# rev_A.net
KiCad netlist of a schematic drawn in EAGLE
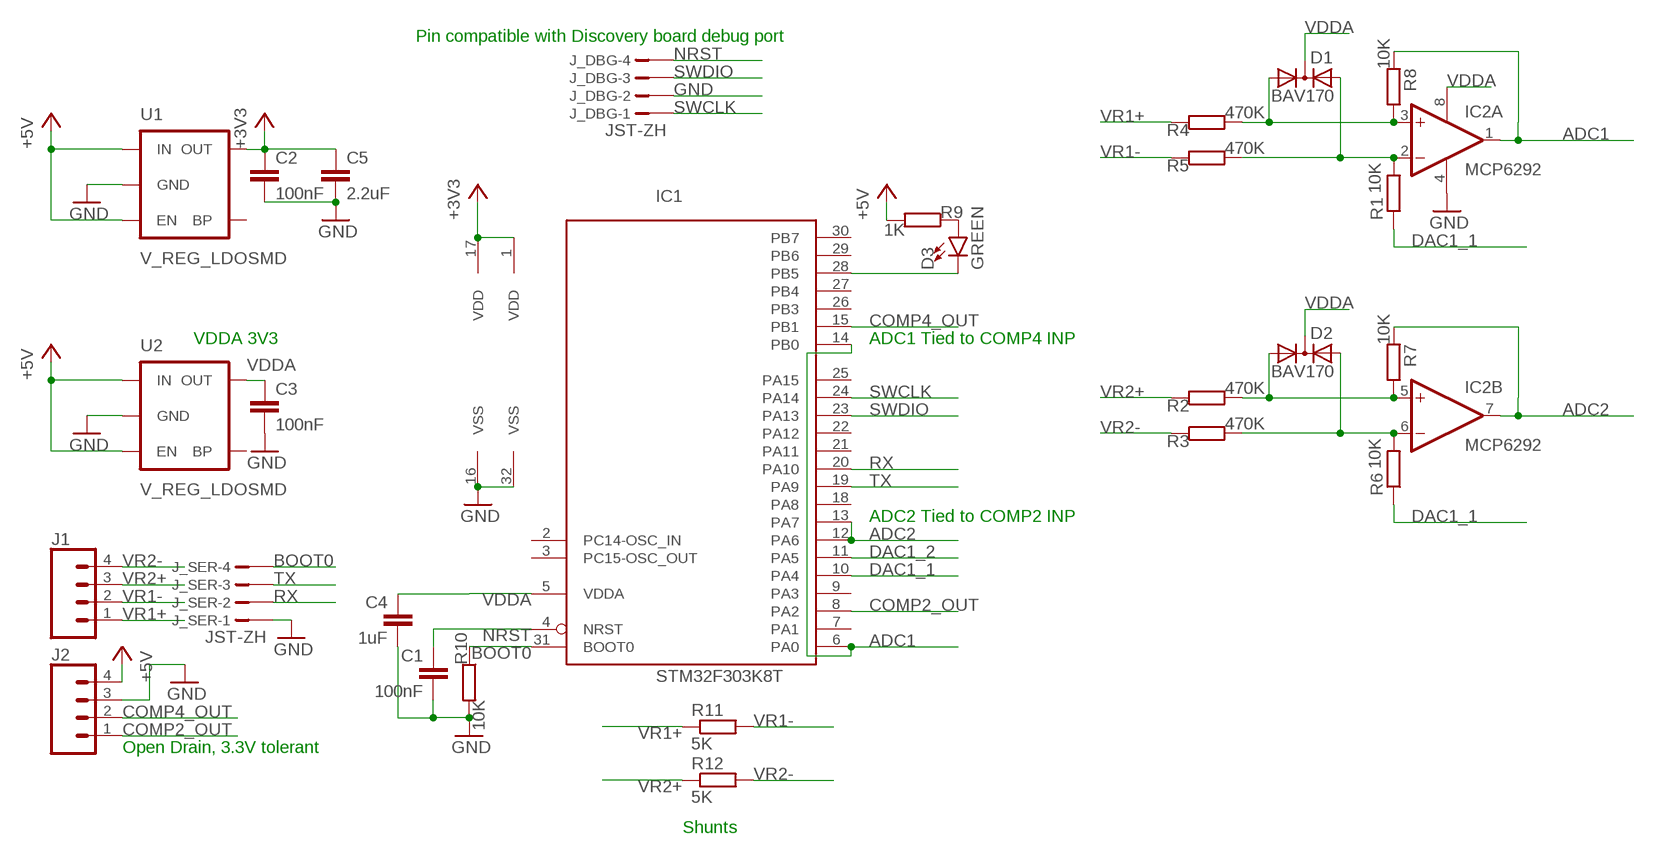
[diagram p0: schematic, sheet 1]

(export (version "E")
  (design (tool "Eeschema 10.0.6"))
  (components
    (comp (ref "C1")
      (value "100nF")
      (footprint "eagle-import:C0603")
      (libsource (lib "eagle-import") (part "C-EUC0603"))
    )
    (comp (ref "C2")
      (value "100nF")
      (footprint "eagle-import:C0603")
      (libsource (lib "eagle-import") (part "C-EUC0603"))
    )
    (comp (ref "C3")
      (value "100nF")
      (footprint "eagle-import:C0603")
      (libsource (lib "eagle-import") (part "C-EUC0603"))
    )
    (comp (ref "C4")
      (value "1uF")
      (footprint "eagle-import:C0603")
      (libsource (lib "eagle-import") (part "C-EUC0603"))
    )
    (comp (ref "C5")
      (value "2.2uF")
      (footprint "eagle-import:C0603")
      (libsource (lib "eagle-import") (part "C-EUC0603"))
    )
    (comp (ref "D1")
      (value "BAV170")
      (footprint "eagle-import:SOT23")
      (libsource (lib "eagle-import") (part "DIODE-2AC|CASOT23"))
    )
    (comp (ref "D2")
      (value "BAV170")
      (footprint "eagle-import:SOT23")
      (libsource (lib "eagle-import") (part "DIODE-2AC|CASOT23"))
    )
    (comp (ref "D3")
      (value "GREEN")
      (footprint "eagle-import:LED-0603")
      (libsource (lib "eagle-import") (part "LED-GREEN0603"))
    )
    (comp (ref "IC1")
      (value "STM32F303K8T")
      (footprint "eagle-import:LQFP32")
      (libsource (lib "eagle-import") (part "STM32L051KT6"))
    )
    (comp (ref "IC2")
      (value "MCP6292")
      (footprint "eagle-import:SO08")
      (libsource (lib "eagle-import") (part "MCP602SN"))
    )
    (comp (ref "J1")
      (value "CONN_04LOCK")
      (footprint "eagle-import:1X04_LOCK")
      (libsource (lib "eagle-import") (part "CONN_04LOCK"))
    )
    (comp (ref "J2")
      (value "CONN_04LOCK")
      (footprint "eagle-import:1X04_LOCK")
      (libsource (lib "eagle-import") (part "CONN_04LOCK"))
    )
    (comp (ref "J_DBG")
      (value "JST-ZH")
      (footprint "eagle-import:B4B-ZR")
      (fields (field (name "MF") "FARNELL") (field (name "MPN") "B4B-ZR(LF)(SN)"))
      (libsource (lib "eagle-import") (part "?4B-ZRB"))
    )
    (comp (ref "J_SER")
      (value "JST-ZH")
      (footprint "eagle-import:B4B-ZR")
      (fields (field (name "MF") "FARNELL") (field (name "MPN") "B4B-ZR(LF)(SN)"))
      (libsource (lib "eagle-import") (part "?4B-ZRB"))
    )
    (comp (ref "R1")
      (value "10K")
      (footprint "eagle-import:R0603")
      (libsource (lib "eagle-import") (part "R-EU_R0603"))
    )
    (comp (ref "R2")
      (value "470K")
      (footprint "eagle-import:R0603")
      (libsource (lib "eagle-import") (part "R-EU_R0603"))
    )
    (comp (ref "R3")
      (value "470K")
      (footprint "eagle-import:R0603")
      (libsource (lib "eagle-import") (part "R-EU_R0603"))
    )
    (comp (ref "R4")
      (value "470K")
      (footprint "eagle-import:R0603")
      (libsource (lib "eagle-import") (part "R-EU_R0603"))
    )
    (comp (ref "R5")
      (value "470K")
      (footprint "eagle-import:R0603")
      (libsource (lib "eagle-import") (part "R-EU_R0603"))
    )
    (comp (ref "R6")
      (value "10K")
      (footprint "eagle-import:R0603")
      (libsource (lib "eagle-import") (part "R-EU_R0603"))
    )
    (comp (ref "R7")
      (value "10K")
      (footprint "eagle-import:R0603")
      (libsource (lib "eagle-import") (part "R-EU_R0603"))
    )
    (comp (ref "R8")
      (value "10K")
      (footprint "eagle-import:R0603")
      (libsource (lib "eagle-import") (part "R-EU_R0603"))
    )
    (comp (ref "R9")
      (value "1K")
      (footprint "eagle-import:R0603")
      (libsource (lib "eagle-import") (part "R-EU_R0603"))
    )
    (comp (ref "R10")
      (value "10K")
      (footprint "eagle-import:R0603")
      (libsource (lib "eagle-import") (part "R-EU_R0603"))
    )
    (comp (ref "R11")
      (value "5K")
      (footprint "eagle-import:0411_12")
      (libsource (lib "eagle-import") (part "R-EU_0411/12"))
    )
    (comp (ref "R12")
      (value "5K")
      (footprint "eagle-import:0411_12")
      (libsource (lib "eagle-import") (part "R-EU_0411/12"))
    )
    (comp (ref "U1")
      (value "V_REG_LDOSMD")
      (footprint "eagle-import:SOT23-5")
      (libsource (lib "eagle-import") (part "V_REG_LDOSMD"))
    )
    (comp (ref "U2")
      (value "V_REG_LDOSMD")
      (footprint "eagle-import:SOT23-5")
      (libsource (lib "eagle-import") (part "V_REG_LDOSMD"))
    )
  )
  (nets
    (net (code "1") (name "+3V3") (class "Default")
      (node (ref "C2") (pin "1") (pinfunction "1_1") (pintype "passive"))
      (node (ref "C5") (pin "1") (pinfunction "1_1") (pintype "passive"))
      (node (ref "IC1") (pin "1") (pinfunction "VDD_1") (pintype "power_in"))
      (node (ref "IC1") (pin "17") (pinfunction "VDD_17") (pintype "power_in"))
      (node (ref "U1") (pin "5") (pinfunction "OUT_5") (pintype "passive"))
    )
    (net (code "2") (name "+5V") (class "Default")
      (node (ref "J2") (pin "4") (pinfunction "4_4") (pintype "passive"))
      (node (ref "R9") (pin "2") (pinfunction "2_2") (pintype "passive"))
      (node (ref "U1") (pin "1") (pinfunction "IN_1") (pintype "input"))
      (node (ref "U1") (pin "3") (pinfunction "EN_3") (pintype "input"))
      (node (ref "U2") (pin "1") (pinfunction "IN_1") (pintype "input"))
      (node (ref "U2") (pin "3") (pinfunction "EN_3") (pintype "input"))
    )
    (net (code "3") (name "/ADC1") (class "Default")
      (node (ref "IC1") (pin "14") (pinfunction "PB0_14") (pintype "bidirectional"))
      (node (ref "IC1") (pin "6") (pinfunction "PA0_6") (pintype "bidirectional"))
      (node (ref "IC2") (pin "1") (pinfunction "OUT_1") (pintype "output"))
      (node (ref "R8") (pin "2") (pinfunction "2_2") (pintype "passive"))
    )
    (net (code "4") (name "/ADC2") (class "Default")
      (node (ref "IC1") (pin "12") (pinfunction "PA6_12") (pintype "bidirectional"))
      (node (ref "IC1") (pin "13") (pinfunction "PA7_13") (pintype "bidirectional"))
      (node (ref "IC2") (pin "7") (pinfunction "OUT_7") (pintype "output"))
      (node (ref "R7") (pin "2") (pinfunction "2_2") (pintype "passive"))
    )
    (net (code "5") (name "/BOOT0") (class "Default")
      (node (ref "IC1") (pin "31") (pinfunction "BOOT0_31") (pintype "input"))
      (node (ref "J_SER") (pin "4") (pinfunction "1_4") (pintype "passive"))
      (node (ref "R10") (pin "1") (pinfunction "1_1") (pintype "passive"))
    )
    (net (code "6") (name "/COMP2_OUT") (class "Default")
      (node (ref "IC1") (pin "8") (pinfunction "PA2_8") (pintype "bidirectional"))
      (node (ref "J2") (pin "1") (pinfunction "1_1") (pintype "passive"))
    )
    (net (code "7") (name "/COMP4_OUT") (class "Default")
      (node (ref "IC1") (pin "15") (pinfunction "PB1_15") (pintype "bidirectional"))
      (node (ref "J2") (pin "2") (pinfunction "2_2") (pintype "passive"))
    )
    (net (code "8") (name "/DAC1_1") (class "Default")
      (node (ref "IC1") (pin "10") (pinfunction "PA4_10") (pintype "bidirectional"))
      (node (ref "R1") (pin "1") (pinfunction "1_1") (pintype "passive"))
      (node (ref "R6") (pin "1") (pinfunction "1_1") (pintype "passive"))
    )
    (net (code "9") (name "/DAC1_2") (class "Default")
      (node (ref "IC1") (pin "11") (pinfunction "PA5_11") (pintype "bidirectional"))
    )
    (net (code "10") (name "/NRST") (class "Default")
      (node (ref "C1") (pin "1") (pinfunction "1_1") (pintype "passive"))
      (node (ref "IC1") (pin "4") (pinfunction "NRST_4") (pintype "bidirectional"))
      (node (ref "J_DBG") (pin "4") (pinfunction "1_4") (pintype "passive"))
    )
    (net (code "11") (name "/RX") (class "Default")
      (node (ref "IC1") (pin "20") (pinfunction "PA10_20") (pintype "bidirectional"))
      (node (ref "J_SER") (pin "2") (pinfunction "1_2") (pintype "passive"))
    )
    (net (code "12") (name "/SWCLK") (class "Default")
      (node (ref "IC1") (pin "24") (pinfunction "PA14_24") (pintype "bidirectional"))
      (node (ref "J_DBG") (pin "1") (pinfunction "1_1") (pintype "passive"))
    )
    (net (code "13") (name "/SWDIO") (class "Default")
      (node (ref "IC1") (pin "23") (pinfunction "PA13_23") (pintype "bidirectional"))
      (node (ref "J_DBG") (pin "3") (pinfunction "1_3") (pintype "passive"))
    )
    (net (code "14") (name "/TX") (class "Default")
      (node (ref "IC1") (pin "19") (pinfunction "PA9_19") (pintype "bidirectional"))
      (node (ref "J_SER") (pin "3") (pinfunction "1_3") (pintype "passive"))
    )
    (net (code "15") (name "/VDDA") (class "Default")
      (node (ref "C3") (pin "1") (pinfunction "1_1") (pintype "passive"))
      (node (ref "C4") (pin "1") (pinfunction "1_1") (pintype "passive"))
      (node (ref "D1") (pin "3") (pinfunction "C_3") (pintype "passive"))
      (node (ref "D2") (pin "3") (pinfunction "C_3") (pintype "passive"))
      (node (ref "IC1") (pin "5") (pinfunction "VDDA_5") (pintype "power_in"))
      (node (ref "IC2") (pin "8") (pinfunction "V+_8") (pintype "power_in"))
      (node (ref "U2") (pin "5") (pinfunction "OUT_5") (pintype "passive"))
    )
    (net (code "16") (name "/VR1+") (class "Default")
      (node (ref "J1") (pin "1") (pinfunction "1_1") (pintype "passive"))
      (node (ref "R11") (pin "1") (pinfunction "1_1") (pintype "passive"))
      (node (ref "R4") (pin "1") (pinfunction "1_1") (pintype "passive"))
    )
    (net (code "17") (name "/VR1-") (class "Default")
      (node (ref "J1") (pin "2") (pinfunction "2_2") (pintype "passive"))
      (node (ref "R11") (pin "2") (pinfunction "2_2") (pintype "passive"))
      (node (ref "R5") (pin "1") (pinfunction "1_1") (pintype "passive"))
    )
    (net (code "18") (name "/VR2+") (class "Default")
      (node (ref "J1") (pin "3") (pinfunction "3_3") (pintype "passive"))
      (node (ref "R12") (pin "1") (pinfunction "1_1") (pintype "passive"))
      (node (ref "R2") (pin "1") (pinfunction "1_1") (pintype "passive"))
    )
    (net (code "19") (name "/VR2-") (class "Default")
      (node (ref "J1") (pin "4") (pinfunction "4_4") (pintype "passive"))
      (node (ref "R12") (pin "2") (pinfunction "2_2") (pintype "passive"))
      (node (ref "R3") (pin "1") (pinfunction "1_1") (pintype "passive"))
    )
    (net (code "20") (name "GND") (class "Default")
      (node (ref "C1") (pin "2") (pinfunction "2_2") (pintype "passive"))
      (node (ref "C2") (pin "2") (pinfunction "2_2") (pintype "passive"))
      (node (ref "C3") (pin "2") (pinfunction "2_2") (pintype "passive"))
      (node (ref "C4") (pin "2") (pinfunction "2_2") (pintype "passive"))
      (node (ref "C5") (pin "2") (pinfunction "2_2") (pintype "passive"))
      (node (ref "IC1") (pin "16") (pinfunction "VSS_16") (pintype "power_in"))
      (node (ref "IC1") (pin "32") (pinfunction "VSS_32") (pintype "power_in"))
      (node (ref "IC2") (pin "4") (pinfunction "V-_4") (pintype "power_in"))
      (node (ref "J2") (pin "3") (pinfunction "3_3") (pintype "passive"))
      (node (ref "J_DBG") (pin "2") (pinfunction "1_2") (pintype "passive"))
      (node (ref "J_SER") (pin "1") (pinfunction "1_1") (pintype "passive"))
      (node (ref "R10") (pin "2") (pinfunction "2_2") (pintype "passive"))
      (node (ref "U1") (pin "2") (pinfunction "GND_2") (pintype "input"))
      (node (ref "U2") (pin "2") (pinfunction "GND_2") (pintype "input"))
    )
    (net (code "21") (name "Net-(D1-A1)") (class "Default")
      (node (ref "D1") (pin "1") (pinfunction "A1_1") (pintype "passive"))
      (node (ref "IC2") (pin "3") (pinfunction "+IN_3") (pintype "input"))
      (node (ref "R4") (pin "2") (pinfunction "2_2") (pintype "passive"))
      (node (ref "R8") (pin "1") (pinfunction "1_1") (pintype "passive"))
    )
    (net (code "22") (name "Net-(D1-A2)") (class "Default")
      (node (ref "D1") (pin "2") (pinfunction "A2_2") (pintype "passive"))
      (node (ref "IC2") (pin "2") (pinfunction "-IN_2") (pintype "input"))
      (node (ref "R1") (pin "2") (pinfunction "2_2") (pintype "passive"))
      (node (ref "R5") (pin "2") (pinfunction "2_2") (pintype "passive"))
    )
    (net (code "23") (name "Net-(D2-A1)") (class "Default")
      (node (ref "D2") (pin "1") (pinfunction "A1_1") (pintype "passive"))
      (node (ref "IC2") (pin "5") (pinfunction "+IN_5") (pintype "input"))
      (node (ref "R2") (pin "2") (pinfunction "2_2") (pintype "passive"))
      (node (ref "R7") (pin "1") (pinfunction "1_1") (pintype "passive"))
    )
    (net (code "24") (name "Net-(D2-A2)") (class "Default")
      (node (ref "D2") (pin "2") (pinfunction "A2_2") (pintype "passive"))
      (node (ref "IC2") (pin "6") (pinfunction "-IN_6") (pintype "input"))
      (node (ref "R3") (pin "2") (pinfunction "2_2") (pintype "passive"))
      (node (ref "R6") (pin "2") (pinfunction "2_2") (pintype "passive"))
    )
    (net (code "25") (name "Net-(D3-PadA)") (class "Default")
      (node (ref "D3") (pin "A") (pinfunction "A_A") (pintype "passive"))
      (node (ref "R9") (pin "1") (pinfunction "1_1") (pintype "passive"))
    )
    (net (code "26") (name "Net-(IC1A-PB5)") (class "Default")
      (node (ref "D3") (pin "C") (pinfunction "C_C") (pintype "passive"))
      (node (ref "IC1") (pin "28") (pinfunction "PB5_28") (pintype "bidirectional"))
    )
    (net (code "27") (name "unconnected-(IC1A-PA1-Pad7)") (class "Default")
      (node (ref "IC1") (pin "7") (pinfunction "PA1_7") (pintype "bidirectional"))
    )
    (net (code "28") (name "unconnected-(IC1A-PA3-Pad9)") (class "Default")
      (node (ref "IC1") (pin "9") (pinfunction "PA3_9") (pintype "bidirectional"))
    )
    (net (code "29") (name "unconnected-(IC1A-PA8-Pad18)") (class "Default")
      (node (ref "IC1") (pin "18") (pinfunction "PA8_18") (pintype "bidirectional"))
    )
    (net (code "30") (name "unconnected-(IC1A-PA11-Pad21)") (class "Default")
      (node (ref "IC1") (pin "21") (pinfunction "PA11_21") (pintype "bidirectional"))
    )
    (net (code "31") (name "unconnected-(IC1A-PA12-Pad22)") (class "Default")
      (node (ref "IC1") (pin "22") (pinfunction "PA12_22") (pintype "bidirectional"))
    )
    (net (code "32") (name "unconnected-(IC1A-PA15-Pad25)") (class "Default")
      (node (ref "IC1") (pin "25") (pinfunction "PA15_25") (pintype "bidirectional"))
    )
    (net (code "33") (name "unconnected-(IC1A-PB3-Pad26)") (class "Default")
      (node (ref "IC1") (pin "26") (pinfunction "PB3_26") (pintype "bidirectional"))
    )
    (net (code "34") (name "unconnected-(IC1A-PB4-Pad27)") (class "Default")
      (node (ref "IC1") (pin "27") (pinfunction "PB4_27") (pintype "bidirectional"))
    )
    (net (code "35") (name "unconnected-(IC1A-PB6-Pad29)") (class "Default")
      (node (ref "IC1") (pin "29") (pinfunction "PB6_29") (pintype "bidirectional"))
    )
    (net (code "36") (name "unconnected-(IC1A-PB7-Pad30)") (class "Default")
      (node (ref "IC1") (pin "30") (pinfunction "PB7_30") (pintype "bidirectional"))
    )
    (net (code "37") (name "unconnected-(IC1A-PC14-OSC_IN-Pad2)") (class "Default")
      (node (ref "IC1") (pin "2") (pinfunction "PC14-OSC_IN_2") (pintype "bidirectional"))
    )
    (net (code "38") (name "unconnected-(IC1A-PC15-OSC_OUT-Pad3)") (class "Default")
      (node (ref "IC1") (pin "3") (pinfunction "PC15-OSC_OUT_3") (pintype "bidirectional"))
    )
    (net (code "39") (name "unconnected-(U1-BP-Pad4)") (class "Default")
      (node (ref "U1") (pin "4") (pinfunction "BP_4") (pintype "input"))
    )
    (net (code "40") (name "unconnected-(U2-BP-Pad4)") (class "Default")
      (node (ref "U2") (pin "4") (pinfunction "BP_4") (pintype "input"))
    )
  )
)
